# Nano_gies.net
KiCad netlist of a schematic drawn in EAGLE
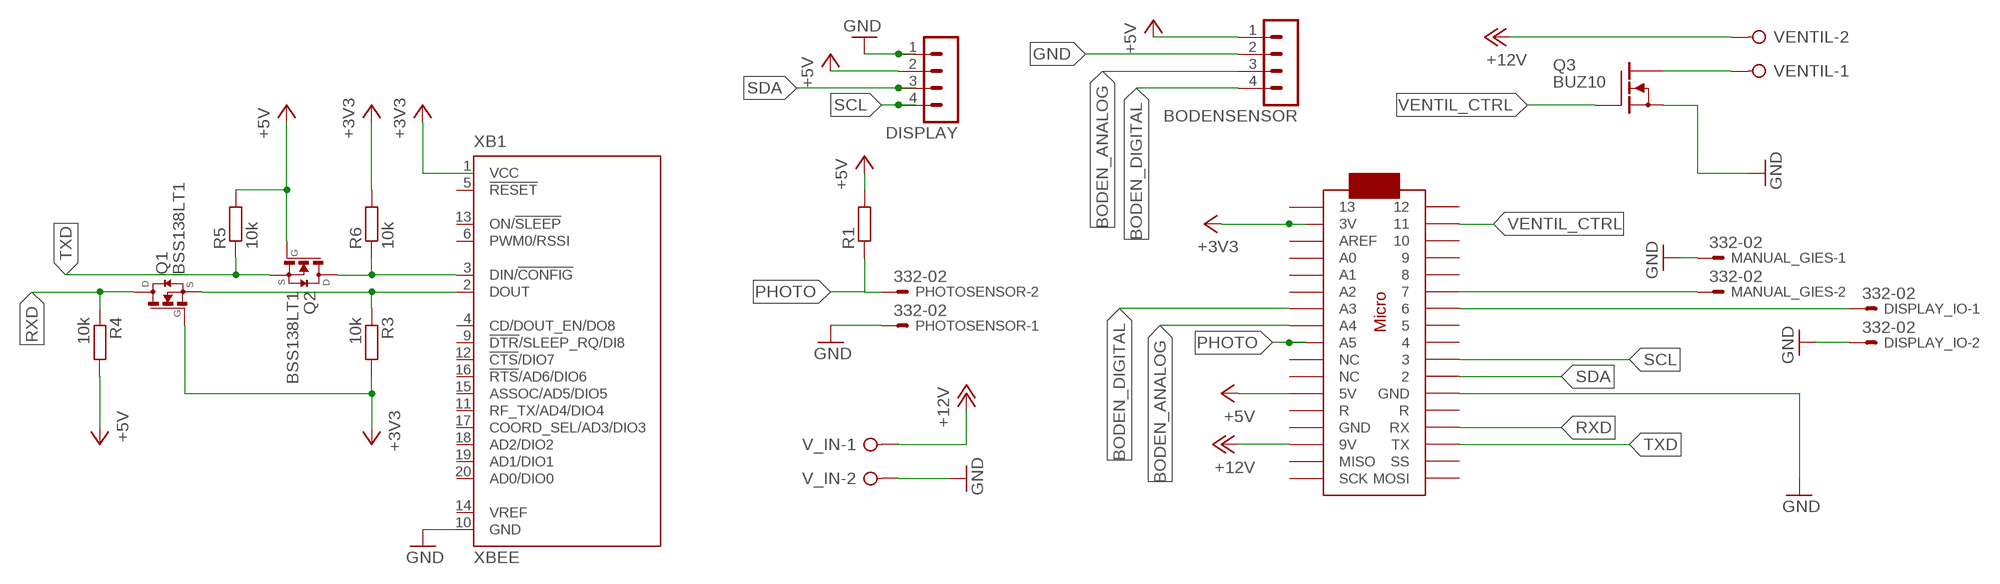
[diagram p0: schematic, sheet 1]

(export (version "E")
  (design (tool "Eeschema 10.0.6"))
  (components
    (comp (ref "BODENSENSOR")
      (value "MA04-1")
      (footprint "eagle-import:MA04-1")
      (libsource (lib "eagle-import") (part "MA04-1"))
    )
    (comp (ref "DISPLAY")
      (value "MA04-1")
      (footprint "eagle-import:MA04-1")
      (libsource (lib "eagle-import") (part "MA04-1"))
    )
    (comp (ref "DISPLAY_IO")
      (value "332-02")
      (footprint "eagle-import:332-02")
      (libsource (lib "eagle-import") (part "332-02"))
    )
    (comp (ref "MANUAL_GIES")
      (value "332-02")
      (footprint "eagle-import:332-02")
      (libsource (lib "eagle-import") (part "332-02"))
    )
    (comp (ref "PHOTOSENSOR")
      (value "332-02")
      (footprint "eagle-import:332-02")
      (libsource (lib "eagle-import") (part "332-02"))
    )
    (comp (ref "Q1")
      (value "BSS138LT1")
      (footprint "eagle-import:SOT23")
      (libsource (lib "eagle-import") (part "BSS138LT1"))
    )
    (comp (ref "Q2")
      (value "BSS138LT1")
      (footprint "eagle-import:SOT23")
      (libsource (lib "eagle-import") (part "BSS138LT1"))
    )
    (comp (ref "Q3")
      (value "BUZ10")
      (footprint "eagle-import:TO220")
      (libsource (lib "eagle-import") (part "BUZ10"))
    )
    (comp (ref "R1")
      (value "R-EU_M0805")
      (footprint "eagle-import:M0805")
      (libsource (lib "eagle-import") (part "R-EU_M0805"))
    )
    (comp (ref "R3")
      (value "10k")
      (footprint "eagle-import:M0805")
      (libsource (lib "eagle-import") (part "R-EU_M0805"))
    )
    (comp (ref "R4")
      (value "10k")
      (footprint "eagle-import:M0805")
      (libsource (lib "eagle-import") (part "R-EU_M0805"))
    )
    (comp (ref "R5")
      (value "10k")
      (footprint "eagle-import:M0805")
      (libsource (lib "eagle-import") (part "R-EU_M0805"))
    )
    (comp (ref "R6")
      (value "10k")
      (footprint "eagle-import:M0805")
      (libsource (lib "eagle-import") (part "R-EU_M0805"))
    )
    (comp (ref "U$1")
      (value "ARDUINOMICRO")
      (footprint "eagle-import:ARDUINOMICRO")
      (libsource (lib "eagle-import") (part "ARDUINOMICRO"))
    )
    (comp (ref "VENTIL")
      (value "W237-02P")
      (footprint "eagle-import:W237-132")
      (libsource (lib "eagle-import") (part "W237-02P"))
    )
    (comp (ref "V_IN")
      (value "W237-02P")
      (footprint "eagle-import:W237-132")
      (libsource (lib "eagle-import") (part "W237-02P"))
    )
    (comp (ref "XB1")
      (value "XBEE")
      (footprint "eagle-import:XBEE")
      (fields (field (name "MPN") "XBP24-Z7UIT-004"))
      (libsource (lib "eagle-import") (part "XBEE"))
    )
  )
  (nets
    (net (code "1") (name "+3V3") (class "Default")
      (node (ref "Q1") (pin "1") (pinfunction "G_1") (pintype "passive"))
      (node (ref "R3") (pin "2") (pinfunction "2_2") (pintype "passive"))
      (node (ref "R6") (pin "2") (pinfunction "2_2") (pintype "passive"))
      (node (ref "U$1") (pin "P$33") (pinfunction "3V_P$33") (pintype "bidirectional"))
      (node (ref "XB1") (pin "1") (pinfunction "VCC_1") (pintype "power_in"))
    )
    (net (code "2") (name "+5V") (class "Default")
      (node (ref "BODENSENSOR") (pin "1") (pinfunction "1_1") (pintype "passive"))
      (node (ref "DISPLAY") (pin "2") (pinfunction "2_2") (pintype "passive"))
      (node (ref "Q2") (pin "1") (pinfunction "G_1") (pintype "passive"))
      (node (ref "R1") (pin "2") (pinfunction "2_2") (pintype "passive"))
      (node (ref "R4") (pin "2") (pinfunction "2_2") (pintype "passive"))
      (node (ref "R5") (pin "2") (pinfunction "2_2") (pintype "passive"))
      (node (ref "U$1") (pin "P$23") (pinfunction "5V_P$23") (pintype "bidirectional"))
    )
    (net (code "3") (name "+12V") (class "Default")
      (node (ref "U$1") (pin "P$20") (pinfunction "9V_P$20") (pintype "bidirectional"))
      (node (ref "VENTIL") (pin "2") (pinfunction "KL_2") (pintype "passive"))
      (node (ref "V_IN") (pin "1") (pinfunction "KL_1") (pintype "passive"))
    )
    (net (code "4") (name "BODEN_ANALOG") (class "Default")
      (node (ref "BODENSENSOR") (pin "3") (pinfunction "3_3") (pintype "passive"))
      (node (ref "U$1") (pin "P$27") (pinfunction "A4_P$27") (pintype "bidirectional"))
    )
    (net (code "5") (name "BODEN_DIGITAL") (class "Default")
      (node (ref "BODENSENSOR") (pin "4") (pinfunction "4_4") (pintype "passive"))
      (node (ref "U$1") (pin "P$28") (pinfunction "A3_P$28") (pintype "bidirectional"))
    )
    (net (code "6") (name "GND") (class "Default")
      (node (ref "BODENSENSOR") (pin "2") (pinfunction "2_2") (pintype "passive"))
      (node (ref "DISPLAY") (pin "1") (pinfunction "1_1") (pintype "passive"))
      (node (ref "DISPLAY_IO") (pin "2") (pinfunction "S_2") (pintype "passive"))
      (node (ref "MANUAL_GIES") (pin "1") (pinfunction "S_1") (pintype "passive"))
      (node (ref "PHOTOSENSOR") (pin "1") (pinfunction "S_1") (pintype "passive"))
      (node (ref "Q3") (pin "3") (pinfunction "S_3") (pintype "passive"))
      (node (ref "U$1") (pin "P$21") (pinfunction "GND_P$21") (pintype "bidirectional"))
      (node (ref "V_IN") (pin "2") (pinfunction "KL_2") (pintype "passive"))
      (node (ref "XB1") (pin "10") (pinfunction "GND_10") (pintype "power_in"))
    )
    (net (code "7") (name "Net-(DISPLAY_IOA-S)") (class "Default")
      (node (ref "DISPLAY_IO") (pin "1") (pinfunction "S_1") (pintype "passive"))
      (node (ref "U$1") (pin "P$7") (pinfunction "6_P$7") (pintype "bidirectional"))
    )
    (net (code "8") (name "Net-(MANUAL_GIESB-S)") (class "Default")
      (node (ref "MANUAL_GIES") (pin "2") (pinfunction "S_2") (pintype "passive"))
      (node (ref "U$1") (pin "P$6") (pinfunction "7_P$6") (pintype "bidirectional"))
    )
    (net (code "9") (name "Net-(Q1-S)") (class "Default")
      (node (ref "Q1") (pin "2") (pinfunction "S_2") (pintype "passive"))
      (node (ref "R3") (pin "1") (pinfunction "1_1") (pintype "passive"))
      (node (ref "XB1") (pin "2") (pinfunction "DOUT_2") (pintype "output"))
    )
    (net (code "10") (name "Net-(Q2-D)") (class "Default")
      (node (ref "Q2") (pin "3") (pinfunction "D_3") (pintype "passive"))
      (node (ref "R6") (pin "1") (pinfunction "1_1") (pintype "passive"))
      (node (ref "XB1") (pin "3") (pinfunction "DIN/~{CONFIG}_3") (pintype "input"))
    )
    (net (code "11") (name "Net-(Q3-D)") (class "Default")
      (node (ref "Q3") (pin "2") (pinfunction "D_2") (pintype "passive"))
      (node (ref "VENTIL") (pin "1") (pinfunction "KL_1") (pintype "passive"))
    )
    (net (code "12") (name "PHOTO") (class "Default")
      (node (ref "PHOTOSENSOR") (pin "2") (pinfunction "S_2") (pintype "passive"))
      (node (ref "R1") (pin "1") (pinfunction "1_1") (pintype "passive"))
      (node (ref "U$1") (pin "P$26") (pinfunction "A5_P$26") (pintype "bidirectional"))
    )
    (net (code "13") (name "RXD") (class "Default")
      (node (ref "Q1") (pin "3") (pinfunction "D_3") (pintype "passive"))
      (node (ref "R4") (pin "1") (pinfunction "1_1") (pintype "passive"))
      (node (ref "U$1") (pin "P$14") (pinfunction "RX_P$14") (pintype "bidirectional"))
    )
    (net (code "14") (name "SCL") (class "Default")
      (node (ref "DISPLAY") (pin "4") (pinfunction "4_4") (pintype "passive"))
      (node (ref "U$1") (pin "P$10") (pinfunction "3_P$10") (pintype "bidirectional"))
    )
    (net (code "15") (name "SDA") (class "Default")
      (node (ref "DISPLAY") (pin "3") (pinfunction "3_3") (pintype "passive"))
      (node (ref "U$1") (pin "P$11") (pinfunction "2_P$11") (pintype "bidirectional"))
    )
    (net (code "16") (name "TXD") (class "Default")
      (node (ref "Q2") (pin "2") (pinfunction "S_2") (pintype "passive"))
      (node (ref "R5") (pin "1") (pinfunction "1_1") (pintype "passive"))
      (node (ref "U$1") (pin "P$15") (pinfunction "TX_P$15") (pintype "bidirectional"))
    )
    (net (code "17") (name "VENTIL_CTRL") (class "Default")
      (node (ref "Q3") (pin "1") (pinfunction "G_1") (pintype "passive"))
      (node (ref "U$1") (pin "P$2") (pinfunction "11_P$2") (pintype "bidirectional"))
    )
    (net (code "18") (name "unconnected-(U$1-4-PadP$9)") (class "Default")
      (node (ref "U$1") (pin "P$9") (pinfunction "4_P$9") (pintype "bidirectional"))
    )
    (net (code "19") (name "unconnected-(U$1-5-PadP$8)") (class "Default")
      (node (ref "U$1") (pin "P$8") (pinfunction "5_P$8") (pintype "bidirectional"))
    )
    (net (code "20") (name "unconnected-(U$1-8-PadP$5)") (class "Default")
      (node (ref "U$1") (pin "P$5") (pinfunction "8_P$5") (pintype "bidirectional"))
    )
    (net (code "21") (name "unconnected-(U$1-9-PadP$4)") (class "Default")
      (node (ref "U$1") (pin "P$4") (pinfunction "9_P$4") (pintype "bidirectional"))
    )
    (net (code "22") (name "unconnected-(U$1-10-PadP$3)") (class "Default")
      (node (ref "U$1") (pin "P$3") (pinfunction "10_P$3") (pintype "bidirectional"))
    )
    (net (code "23") (name "unconnected-(U$1-12-PadP$1)") (class "Default")
      (node (ref "U$1") (pin "P$1") (pinfunction "12_P$1") (pintype "bidirectional"))
    )
    (net (code "24") (name "unconnected-(U$1-13-PadP$34)") (class "Default")
      (node (ref "U$1") (pin "P$34") (pinfunction "13_P$34") (pintype "bidirectional"))
    )
    (net (code "25") (name "unconnected-(U$1-A0-PadP$31)") (class "Default")
      (node (ref "U$1") (pin "P$31") (pinfunction "A0_P$31") (pintype "bidirectional"))
    )
    (net (code "26") (name "unconnected-(U$1-A1-PadP$30)") (class "Default")
      (node (ref "U$1") (pin "P$30") (pinfunction "A1_P$30") (pintype "bidirectional"))
    )
    (net (code "27") (name "unconnected-(U$1-A2-PadP$29)") (class "Default")
      (node (ref "U$1") (pin "P$29") (pinfunction "A2_P$29") (pintype "bidirectional"))
    )
    (net (code "28") (name "unconnected-(U$1-AREF-PadP$32)") (class "Default")
      (node (ref "U$1") (pin "P$32") (pinfunction "AREF_P$32") (pintype "bidirectional"))
    )
    (net (code "29") (name "unconnected-(U$1-GND-PadP$12)") (class "Default")
      (node (ref "U$1") (pin "P$12") (pinfunction "GND_P$12") (pintype "bidirectional"))
    )
    (net (code "30") (name "unconnected-(U$1-MISO-PadP$19)") (class "Default")
      (node (ref "U$1") (pin "P$19") (pinfunction "MISO_P$19") (pintype "bidirectional"))
    )
    (net (code "31") (name "unconnected-(U$1-MOSI-PadP$17)") (class "Default")
      (node (ref "U$1") (pin "P$17") (pinfunction "MOSI_P$17") (pintype "bidirectional"))
    )
    (net (code "32") (name "unconnected-(U$1-NC-PadP$24)") (class "Default")
      (node (ref "U$1") (pin "P$24") (pinfunction "NC_P$24") (pintype "bidirectional"))
    )
    (net (code "33") (name "unconnected-(U$1-NC-PadP$25)") (class "Default")
      (node (ref "U$1") (pin "P$25") (pinfunction "NC_P$25") (pintype "bidirectional"))
    )
    (net (code "34") (name "unconnected-(U$1-R-PadP$13)") (class "Default")
      (node (ref "U$1") (pin "P$13") (pinfunction "R_P$13") (pintype "bidirectional"))
    )
    (net (code "35") (name "unconnected-(U$1-R-PadP$22)") (class "Default")
      (node (ref "U$1") (pin "P$22") (pinfunction "R_P$22") (pintype "bidirectional"))
    )
    (net (code "36") (name "unconnected-(U$1-SCK-PadP$18)") (class "Default")
      (node (ref "U$1") (pin "P$18") (pinfunction "SCK_P$18") (pintype "bidirectional"))
    )
    (net (code "37") (name "unconnected-(U$1-SS-PadP$16)") (class "Default")
      (node (ref "U$1") (pin "P$16") (pinfunction "SS_P$16") (pintype "bidirectional"))
    )
    (net (code "38") (name "unconnected-(XB1-AD0{slash}DIO0-Pad20)") (class "Default")
      (node (ref "XB1") (pin "20") (pinfunction "AD0/DIO0_20") (pintype "bidirectional"))
    )
    (net (code "39") (name "unconnected-(XB1-AD1{slash}DIO1-Pad19)") (class "Default")
      (node (ref "XB1") (pin "19") (pinfunction "AD1/DIO1_19") (pintype "bidirectional"))
    )
    (net (code "40") (name "unconnected-(XB1-AD2{slash}DIO2-Pad18)") (class "Default")
      (node (ref "XB1") (pin "18") (pinfunction "AD2/DIO2_18") (pintype "bidirectional"))
    )
    (net (code "41") (name "unconnected-(XB1-ASSOC{slash}AD5{slash}DIO5-Pad15)") (class "Default")
      (node (ref "XB1") (pin "15") (pinfunction "ASSOC/AD5/DIO5_15") (pintype "bidirectional"))
    )
    (net (code "42") (name "unconnected-(XB1-CD{slash}DOUT_EN{slash}DO8-Pad4)") (class "Default")
      (node (ref "XB1") (pin "4") (pinfunction "CD/DOUT_EN/DO8_4") (pintype "output"))
    )
    (net (code "43") (name "unconnected-(XB1-COORD_SEL{slash}AD3{slash}DIO3-Pad17)") (class "Default")
      (node (ref "XB1") (pin "17") (pinfunction "COORD_SEL/AD3/DIO3_17") (pintype "bidirectional"))
    )
    (net (code "44") (name "unconnected-(XB1-ON{slash}~{SLEEP}-Pad13)") (class "Default")
      (node (ref "XB1") (pin "13") (pinfunction "ON/~{SLEEP}_13") (pintype "output"))
    )
    (net (code "45") (name "unconnected-(XB1-PWM0{slash}RSSI-Pad6)") (class "Default")
      (node (ref "XB1") (pin "6") (pinfunction "PWM0/RSSI_6") (pintype "output"))
    )
    (net (code "46") (name "unconnected-(XB1-RF_TX{slash}AD4{slash}DIO4-Pad11)") (class "Default")
      (node (ref "XB1") (pin "11") (pinfunction "RF_TX/AD4/DIO4_11") (pintype "bidirectional"))
    )
    (net (code "47") (name "unconnected-(XB1-VREF-Pad14)") (class "Default")
      (node (ref "XB1") (pin "14") (pinfunction "VREF_14") (pintype "input"))
    )
    (net (code "48") (name "unconnected-(XB1-~{CTS}{slash}DIO7-Pad12)") (class "Default")
      (node (ref "XB1") (pin "12") (pinfunction "~{CTS}/DIO7_12") (pintype "bidirectional"))
    )
    (net (code "49") (name "unconnected-(XB1-~{DTR}{slash}SLEEP_RQ{slash}DI8-Pad9)") (class "Default")
      (node (ref "XB1") (pin "9") (pinfunction "~{DTR}/SLEEP_RQ/DI8_9") (pintype "bidirectional"))
    )
    (net (code "50") (name "unconnected-(XB1-~{RESET}-Pad5)") (class "Default")
      (node (ref "XB1") (pin "5") (pinfunction "~{RESET}_5") (pintype "input"))
    )
    (net (code "51") (name "unconnected-(XB1-~{RTS}{slash}AD6{slash}DIO6-Pad16)") (class "Default")
      (node (ref "XB1") (pin "16") (pinfunction "~{RTS}/AD6/DIO6_16") (pintype "bidirectional"))
    )
  )
)
